# design.net
KiCad netlist of a schematic drawn in Altium Designer
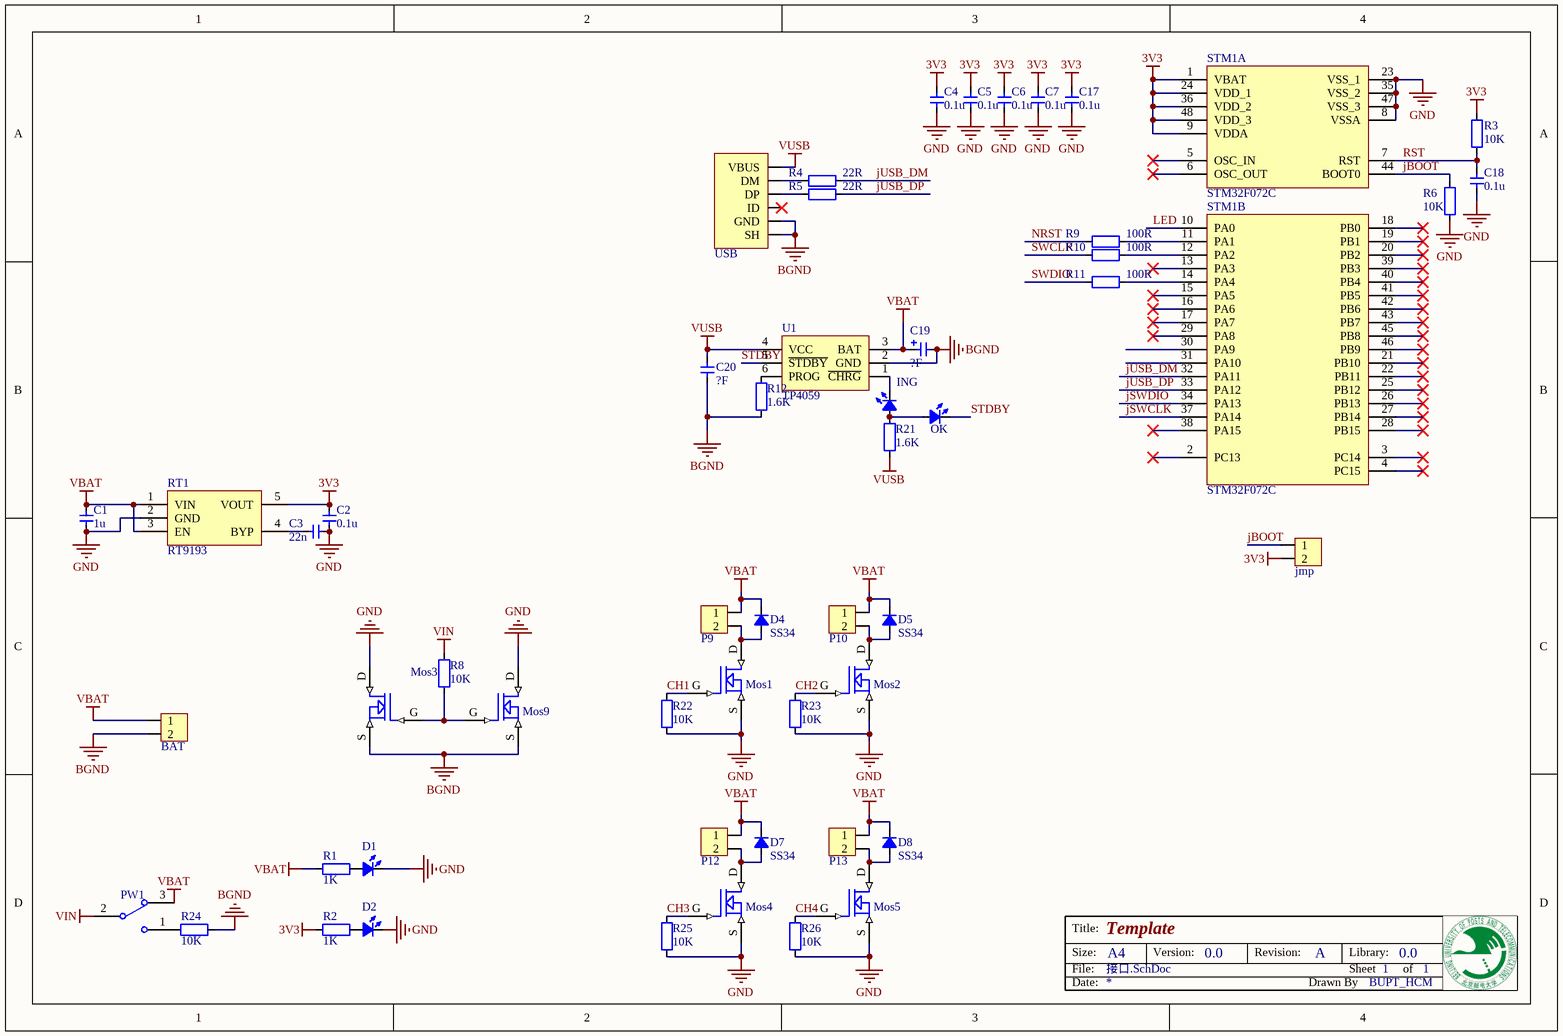
[diagram p0: 接口.SchDoc]

(export (version "E")
  (design (tool "Eeschema 10.0.6"))
  (components
    (comp (ref "BAT")
      (value "HDR1x2_2.54")
      (footprint "PCB_ConnectorHDR:HDR1X2_2.54_90")
      (description "Header")
      (libsource (lib "SCH_ConnectorHDR") (part "HDR1x2_2.54"))
    )
    (comp (ref "C1")
      (value "1u")
      (footprint "PCB_PassiveCap:CAP_0603")
      (description "Capacitor")
      (fields (field (name "Comment") "Cap_0603"))
      (libsource (lib "SCH_Passive") (part "Cap_0603"))
    )
    (comp (ref "C2")
      (value "0.1u")
      (footprint "PCB_PassiveCap:CAP_0603")
      (description "Capacitor")
      (fields (field (name "Comment") "Cap_0603"))
      (libsource (lib "SCH_Passive") (part "Cap_0603"))
    )
    (comp (ref "C3")
      (value "22n")
      (footprint "PCB_PassiveCap:CAP_0603")
      (description "Capacitor")
      (fields (field (name "Comment") "Cap_0603"))
      (libsource (lib "SCH_Passive") (part "Cap_0603"))
    )
    (comp (ref "C4")
      (value "0.1u")
      (footprint "PCB_PassiveCap:CAP_0603")
      (description "Capacitor")
      (fields (field (name "Comment") "Cap_0603"))
      (libsource (lib "SCH_Passive") (part "Cap_0603"))
    )
    (comp (ref "C5")
      (value "0.1u")
      (footprint "PCB_PassiveCap:CAP_0603")
      (description "Capacitor")
      (fields (field (name "Comment") "Cap_0603"))
      (libsource (lib "SCH_Passive") (part "Cap_0603"))
    )
    (comp (ref "C6")
      (value "0.1u")
      (footprint "PCB_PassiveCap:CAP_0603")
      (description "Capacitor")
      (fields (field (name "Comment") "Cap_0603"))
      (libsource (lib "SCH_Passive") (part "Cap_0603"))
    )
    (comp (ref "C7")
      (value "0.1u")
      (footprint "PCB_PassiveCap:CAP_0603")
      (description "Capacitor")
      (fields (field (name "Comment") "Cap_0603"))
      (libsource (lib "SCH_Passive") (part "Cap_0603"))
    )
    (comp (ref "C17")
      (value "0.1u")
      (footprint "PCB_PassiveCap:CAP_0603")
      (description "Capacitor")
      (fields (field (name "Comment") "Cap_0603"))
      (libsource (lib "SCH_Passive") (part "Cap_0603"))
    )
    (comp (ref "C18")
      (value "0.1u")
      (footprint "PCB_PassiveCap:CAP_0603")
      (description "Capacitor")
      (fields (field (name "Comment") "Cap_0603"))
      (libsource (lib "SCH_Passive") (part "Cap_0603"))
    )
    (comp (ref "C19")
      (value "?F")
      (footprint "PCB_PassiveCap:CAP_TAN_D2917")
      (description "Capacitor")
      (fields (field (name "Comment") "Cap_Tan_2917"))
      (libsource (lib "SCH_Passive") (part "Cap_Tan_2917"))
    )
    (comp (ref "C20")
      (value "?F")
      (footprint "PCB_PassiveCap:CAP_0805")
      (description "Capacitor")
      (fields (field (name "Comment") "Cap_0805"))
      (libsource (lib "SCH_Passive") (part "Cap_0805"))
    )
    (comp (ref "D1")
      (value "LED_0805")
      (footprint "PCB_ActiveLED:LED_0805_YELLOW")
      (description "LED")
      (libsource (lib "SCH_Active") (part "LED_0805"))
    )
    (comp (ref "D2")
      (value "LED_0805")
      (footprint "PCB_ActiveLED:LED_0805_YELLOW")
      (description "LED")
      (libsource (lib "SCH_Active") (part "LED_0805"))
    )
    (comp (ref "D4")
      (value "SS34")
      (footprint "PCB_ActiveDIO:DO-214AC")
      (description "Diode")
      (fields (field (name "Comment") "Diode_SMA"))
      (libsource (lib "SCH_Active") (part "Diode_SMA"))
    )
    (comp (ref "D5")
      (value "SS34")
      (footprint "PCB_ActiveDIO:DO-214AC")
      (description "Diode")
      (fields (field (name "Comment") "Diode_SMA"))
      (libsource (lib "SCH_Active") (part "Diode_SMA"))
    )
    (comp (ref "D7")
      (value "SS34")
      (footprint "PCB_ActiveDIO:DO-214AC")
      (description "Diode")
      (fields (field (name "Comment") "Diode_SMA"))
      (libsource (lib "SCH_Active") (part "Diode_SMA"))
    )
    (comp (ref "D8")
      (value "SS34")
      (footprint "PCB_ActiveDIO:DO-214AC")
      (description "Diode")
      (fields (field (name "Comment") "Diode_SMA"))
      (libsource (lib "SCH_Active") (part "Diode_SMA"))
    )
    (comp (ref "ING")
      (value "LED_0805")
      (footprint "PCB_ActiveLED:LED_0805_RED")
      (description "LED")
      (libsource (lib "SCH_Active") (part "LED_0805"))
    )
    (comp (ref "jmp")
      (value "HDR1x2_2.54")
      (footprint "PCB_ConnectorHDR:HDR1X2_2.54_180")
      (description "Header")
      (libsource (lib "SCH_ConnectorHDR") (part "HDR1x2_2.54"))
    )
    (comp (ref "Mos1")
      (value "MOSFET N")
      (footprint "Nmos_SOT23")
      (description "MOS SOT23")
      (libsource (lib "SCH_Active") (part "MOSFET N"))
    )
    (comp (ref "Mos2")
      (value "MOSFET N")
      (footprint "Nmos_SOT23")
      (description "MOS SOT23")
      (libsource (lib "SCH_Active") (part "MOSFET N"))
    )
    (comp (ref "Mos3")
      (value "MOSFET N")
      (footprint "Nmos_SOT23")
      (description "MOS SOT23")
      (libsource (lib "SCH_Active") (part "MOSFET N"))
    )
    (comp (ref "Mos4")
      (value "MOSFET N")
      (footprint "Nmos_SOT23")
      (description "MOS SOT23")
      (libsource (lib "SCH_Active") (part "MOSFET N"))
    )
    (comp (ref "Mos5")
      (value "MOSFET N")
      (footprint "Nmos_SOT23")
      (description "MOS SOT23")
      (libsource (lib "SCH_Active") (part "MOSFET N"))
    )
    (comp (ref "Mos9")
      (value "MOSFET N")
      (footprint "Nmos_SOT23")
      (description "MOS SOT23")
      (libsource (lib "SCH_Active") (part "MOSFET N"))
    )
    (comp (ref "OK")
      (value "LED_0805")
      (footprint "PCB_ActiveLED:LED_0805_GREEN")
      (description "LED")
      (libsource (lib "SCH_Active") (part "LED_0805"))
    )
    (comp (ref "P9")
      (value "HDR1x2_2.54")
      (footprint "PCB_ConnectorHDR:HDR1X2_2.54_180")
      (description "Header")
      (libsource (lib "SCH_ConnectorHDR") (part "HDR1x2_2.54T"))
    )
    (comp (ref "P10")
      (value "HDR1x2_2.54")
      (footprint "PCB_ConnectorHDR:HDR1X2_2.54_180")
      (description "Header")
      (libsource (lib "SCH_ConnectorHDR") (part "HDR1x2_2.54T"))
    )
    (comp (ref "P12")
      (value "HDR1x2_2.54")
      (footprint "PCB_ConnectorHDR:HDR1X2_2.54_180")
      (description "Header")
      (libsource (lib "SCH_ConnectorHDR") (part "HDR1x2_2.54T"))
    )
    (comp (ref "P13")
      (value "HDR1x2_2.54")
      (footprint "PCB_ConnectorHDR:HDR1X2_2.54_180")
      (description "Header")
      (libsource (lib "SCH_ConnectorHDR") (part "HDR1x2_2.54T"))
    )
    (comp (ref "PW1")
      (value "SwitchSPDT_2.8x6.6_90")
      (footprint "PCB_Switch:SwitchSPDT_2.8X6.6_90")
      (description "Switch")
      (libsource (lib "SCH_Switch") (part "SwitchSPDT_2.8x6.6_90"))
    )
    (comp (ref "R1")
      (value "1K")
      (footprint "PCB_PassiveRes:RES_0603")
      (description "Resistor")
      (fields (field (name "Comment") "Res_0603"))
      (libsource (lib "SCH_Passive") (part "Res_0603"))
    )
    (comp (ref "R2")
      (value "1K")
      (footprint "PCB_PassiveRes:RES_0603")
      (description "Resistor")
      (fields (field (name "Comment") "Res_0603"))
      (libsource (lib "SCH_Passive") (part "Res_0603"))
    )
    (comp (ref "R3")
      (value "10K")
      (footprint "PCB_PassiveRes:RES_0603")
      (description "Resistor")
      (fields (field (name "Comment") "Res_0603"))
      (libsource (lib "") (part "Res_0603_1"))
    )
    (comp (ref "R4")
      (value "22R")
      (footprint "PCB_PassiveRes:RES_0603")
      (description "Resistor")
      (fields (field (name "Comment") "Res_0603"))
      (libsource (lib "SCH_Passive") (part "Res_0603"))
    )
    (comp (ref "R5")
      (value "22R")
      (footprint "PCB_PassiveRes:RES_0603")
      (description "Resistor")
      (fields (field (name "Comment") "Res_0603"))
      (libsource (lib "SCH_Passive") (part "Res_0603"))
    )
    (comp (ref "R6")
      (value "10K")
      (footprint "PCB_PassiveRes:RES_0603")
      (description "Resistor")
      (fields (field (name "Comment") "Res_0603"))
      (libsource (lib "") (part "Res_0603_1"))
    )
    (comp (ref "R8")
      (value "10K")
      (footprint "PCB_PassiveRes:RES_0603")
      (description "Resistor")
      (fields (field (name "Comment") "Res_0603"))
      (libsource (lib "") (part "Res_0603_1"))
    )
    (comp (ref "R9")
      (value "100R")
      (footprint "PCB_PassiveRes:RES_0603")
      (description "Resistor")
      (fields (field (name "Comment") "Res_0603"))
      (libsource (lib "SCH_Passive") (part "Res_0603"))
    )
    (comp (ref "R10")
      (value "100R")
      (footprint "PCB_PassiveRes:RES_0603")
      (description "Resistor")
      (fields (field (name "Comment") "Res_0603"))
      (libsource (lib "SCH_Passive") (part "Res_0603"))
    )
    (comp (ref "R11")
      (value "100R")
      (footprint "PCB_PassiveRes:RES_0603")
      (description "Resistor")
      (fields (field (name "Comment") "Res_0603"))
      (libsource (lib "SCH_Passive") (part "Res_0603"))
    )
    (comp (ref "R12")
      (value "1.6K")
      (footprint "PCB_PassiveRes:RES_0603")
      (description "Resistor")
      (fields (field (name "Comment") "Res_0603"))
      (libsource (lib "") (part "Res_0603_2"))
    )
    (comp (ref "R21")
      (value "1.6K")
      (footprint "PCB_PassiveRes:RES_0603")
      (description "Resistor")
      (fields (field (name "Comment") "Res_0603"))
      (libsource (lib "") (part "Res_0603_2"))
    )
    (comp (ref "R22")
      (value "10K")
      (footprint "PCB_PassiveRes:RES_0603")
      (description "Resistor")
      (fields (field (name "Comment") "Res_0603"))
      (libsource (lib "") (part "Res_0603_1"))
    )
    (comp (ref "R23")
      (value "10K")
      (footprint "PCB_PassiveRes:RES_0603")
      (description "Resistor")
      (fields (field (name "Comment") "Res_0603"))
      (libsource (lib "") (part "Res_0603_1"))
    )
    (comp (ref "R24")
      (value "10K")
      (footprint "PCB_PassiveRes:RES_0603")
      (description "Resistor")
      (fields (field (name "Comment") "Res_0603"))
      (libsource (lib "SCH_Passive") (part "Res_0603"))
    )
    (comp (ref "R25")
      (value "10K")
      (footprint "PCB_PassiveRes:RES_0603")
      (description "Resistor")
      (fields (field (name "Comment") "Res_0603"))
      (libsource (lib "") (part "Res_0603_1"))
    )
    (comp (ref "R26")
      (value "10K")
      (footprint "PCB_PassiveRes:RES_0603")
      (description "Resistor")
      (fields (field (name "Comment") "Res_0603"))
      (libsource (lib "") (part "Res_0603_1"))
    )
    (comp (ref "RT1")
      (value "RT9193")
      (footprint "PCB_IntegratedCircuit:SOT23-5")
      (description "Power")
      (libsource (lib "SCH_IntegratedCircuit") (part "RT9193"))
    )
    (comp (ref "STM1")
      (value "STM32F072C")
      (footprint "PCB_IntegratedCircuit:LQFP_P0.5_48")
      (description "MCU")
      (libsource (lib "SCH_IntegratedCircuit") (part "STM32F103C"))
    )
    (comp (ref "U1")
      (value "TP4059")
      (footprint "SOT23-6")
      (libsource (lib "SCH_IntegratedCircuit") (part "TP4059"))
    )
    (comp (ref "USB")
      (value "USB_Micro")
      (footprint "PCB_USB:USB_Micro-AB")
      (description "USB")
      (libsource (lib "SCH_USB") (part "USB_Micro"))
    )
  )
  (nets
    (net (code "1") (name "/CH1") (class "Default")
      (node (ref "Mos1") (pin "G") (pinfunction "G_G") (pintype "input"))
      (node (ref "R22") (pin "2") (pinfunction "2_2") (pintype "passive"))
    )
    (net (code "2") (name "/CH2") (class "Default")
      (node (ref "Mos2") (pin "G") (pinfunction "G_G") (pintype "input"))
      (node (ref "R23") (pin "2") (pinfunction "2_2") (pintype "passive"))
    )
    (net (code "3") (name "/CH3") (class "Default")
      (node (ref "Mos4") (pin "G") (pinfunction "G_G") (pintype "input"))
      (node (ref "R25") (pin "2") (pinfunction "2_2") (pintype "passive"))
    )
    (net (code "4") (name "/CH4") (class "Default")
      (node (ref "Mos5") (pin "G") (pinfunction "G_G") (pintype "input"))
      (node (ref "R26") (pin "2") (pinfunction "2_2") (pintype "passive"))
    )
    (net (code "5") (name "/LED") (class "Default")
      (node (ref "STM1") (pin "10") (pinfunction "PA0_10") (pintype "passive"))
    )
    (net (code "6") (name "/NRST") (class "Default")
      (node (ref "R9") (pin "1") (pinfunction "1_1") (pintype "passive"))
    )
    (net (code "7") (name "/RST") (class "Default")
      (node (ref "C18") (pin "2") (pinfunction "2_2") (pintype "passive"))
      (node (ref "R3") (pin "1") (pinfunction "1_1") (pintype "passive"))
      (node (ref "STM1") (pin "7") (pinfunction "RST_7") (pintype "passive"))
    )
    (net (code "8") (name "/STDBY") (class "Default")
      (node (ref "OK") (pin "2") (pinfunction "K_2") (pintype "passive"))
      (node (ref "U1") (pin "5") (pinfunction "~{STDBY}_5") (pintype "passive"))
    )
    (net (code "9") (name "/SWCLK") (class "Default")
      (node (ref "R10") (pin "1") (pinfunction "1_1") (pintype "passive"))
    )
    (net (code "10") (name "/SWDIO") (class "Default")
      (node (ref "R11") (pin "1") (pinfunction "1_1") (pintype "passive"))
    )
    (net (code "11") (name "/jBOOT") (class "Default")
      (node (ref "R6") (pin "2") (pinfunction "2_2") (pintype "passive"))
      (node (ref "STM1") (pin "44") (pinfunction "BOOT0_44") (pintype "passive"))
      (node (ref "jmp") (pin "1") (pinfunction "1_1") (pintype "passive"))
    )
    (net (code "12") (name "/jSWCLK") (class "Default")
      (node (ref "STM1") (pin "37") (pinfunction "PA14_37") (pintype "passive"))
    )
    (net (code "13") (name "/jSWDIO") (class "Default")
      (node (ref "STM1") (pin "34") (pinfunction "PA13_34") (pintype "passive"))
    )
    (net (code "14") (name "/jUSB_DM") (class "Default")
      (node (ref "R4") (pin "2") (pinfunction "2_2") (pintype "passive"))
      (node (ref "STM1") (pin "32") (pinfunction "PA11_32") (pintype "passive"))
    )
    (net (code "15") (name "/jUSB_DP") (class "Default")
      (node (ref "R5") (pin "2") (pinfunction "2_2") (pintype "passive"))
      (node (ref "STM1") (pin "33") (pinfunction "PA12_33") (pintype "passive"))
    )
    (net (code "16") (name "3V3") (class "Default")
      (node (ref "C17") (pin "2") (pinfunction "2_2") (pintype "passive"))
      (node (ref "C2") (pin "2") (pinfunction "2_2") (pintype "passive"))
      (node (ref "C4") (pin "1") (pinfunction "1_1") (pintype "passive"))
      (node (ref "C5") (pin "1") (pinfunction "1_1") (pintype "passive"))
      (node (ref "C6") (pin "1") (pinfunction "1_1") (pintype "passive"))
      (node (ref "C7") (pin "1") (pinfunction "1_1") (pintype "passive"))
      (node (ref "R2") (pin "1") (pinfunction "1_1") (pintype "passive"))
      (node (ref "R3") (pin "2") (pinfunction "2_2") (pintype "passive"))
      (node (ref "RT1") (pin "5") (pinfunction "VOUT_5") (pintype "passive"))
      (node (ref "STM1") (pin "1") (pinfunction "VBAT_1") (pintype "passive"))
      (node (ref "STM1") (pin "24") (pinfunction "VDD_1_24") (pintype "passive"))
      (node (ref "STM1") (pin "36") (pinfunction "VDD_2_36") (pintype "passive"))
      (node (ref "STM1") (pin "48") (pinfunction "VDD_3_48") (pintype "passive"))
      (node (ref "STM1") (pin "9") (pinfunction "VDDA_9") (pintype "passive"))
      (node (ref "jmp") (pin "2") (pinfunction "2_2") (pintype "passive"))
    )
    (net (code "17") (name "BGND") (class "Default")
      (node (ref "BAT") (pin "2") (pinfunction "2_2") (pintype "passive"))
      (node (ref "C19") (pin "2") (pinfunction "2_2") (pintype "passive"))
      (node (ref "C20") (pin "1") (pinfunction "1_1") (pintype "passive"))
      (node (ref "Mos3") (pin "S") (pinfunction "S_S") (pintype "input"))
      (node (ref "Mos9") (pin "S") (pinfunction "S_S") (pintype "input"))
      (node (ref "R12") (pin "2") (pinfunction "2_2") (pintype "passive"))
      (node (ref "R24") (pin "2") (pinfunction "2_2") (pintype "passive"))
      (node (ref "U1") (pin "2") (pinfunction "GND_2") (pintype "passive"))
      (node (ref "USB") (pin "0") (pinfunction "SH_0") (pintype "passive"))
      (node (ref "USB") (pin "5") (pinfunction "GND_5") (pintype "passive"))
    )
    (net (code "18") (name "GND") (class "Default")
      (node (ref "C1") (pin "1") (pinfunction "1_1") (pintype "passive"))
      (node (ref "C17") (pin "1") (pinfunction "1_1") (pintype "passive"))
      (node (ref "C18") (pin "1") (pinfunction "1_1") (pintype "passive"))
      (node (ref "C2") (pin "1") (pinfunction "1_1") (pintype "passive"))
      (node (ref "C3") (pin "1") (pinfunction "1_1") (pintype "passive"))
      (node (ref "C4") (pin "2") (pinfunction "2_2") (pintype "passive"))
      (node (ref "C5") (pin "2") (pinfunction "2_2") (pintype "passive"))
      (node (ref "C6") (pin "2") (pinfunction "2_2") (pintype "passive"))
      (node (ref "C7") (pin "2") (pinfunction "2_2") (pintype "passive"))
      (node (ref "D1") (pin "2") (pinfunction "K_2") (pintype "passive"))
      (node (ref "D2") (pin "2") (pinfunction "K_2") (pintype "passive"))
      (node (ref "Mos1") (pin "S") (pinfunction "S_S") (pintype "input"))
      (node (ref "Mos2") (pin "S") (pinfunction "S_S") (pintype "input"))
      (node (ref "Mos3") (pin "D") (pinfunction "D_D") (pintype "input"))
      (node (ref "Mos4") (pin "S") (pinfunction "S_S") (pintype "input"))
      (node (ref "Mos5") (pin "S") (pinfunction "S_S") (pintype "input"))
      (node (ref "Mos9") (pin "D") (pinfunction "D_D") (pintype "input"))
      (node (ref "R22") (pin "1") (pinfunction "1_1") (pintype "passive"))
      (node (ref "R23") (pin "1") (pinfunction "1_1") (pintype "passive"))
      (node (ref "R25") (pin "1") (pinfunction "1_1") (pintype "passive"))
      (node (ref "R26") (pin "1") (pinfunction "1_1") (pintype "passive"))
      (node (ref "R6") (pin "1") (pinfunction "1_1") (pintype "passive"))
      (node (ref "RT1") (pin "2") (pinfunction "GND_2") (pintype "passive"))
      (node (ref "STM1") (pin "23") (pinfunction "VSS_1_23") (pintype "passive"))
      (node (ref "STM1") (pin "35") (pinfunction "VSS_2_35") (pintype "passive"))
      (node (ref "STM1") (pin "47") (pinfunction "VSS_3_47") (pintype "passive"))
      (node (ref "STM1") (pin "8") (pinfunction "VSSA_8") (pintype "passive"))
    )
    (net (code "19") (name "Net-(D1-A)") (class "Default")
      (node (ref "D1") (pin "1") (pinfunction "A_1") (pintype "passive"))
      (node (ref "R1") (pin "2") (pinfunction "2_2") (pintype "passive"))
    )
    (net (code "20") (name "Net-(D2-A)") (class "Default")
      (node (ref "D2") (pin "1") (pinfunction "A_1") (pintype "passive"))
      (node (ref "R2") (pin "2") (pinfunction "2_2") (pintype "passive"))
    )
    (net (code "21") (name "Net-(D4-A)") (class "Default")
      (node (ref "D4") (pin "1") (pinfunction "A_1") (pintype "passive"))
      (node (ref "Mos1") (pin "D") (pinfunction "D_D") (pintype "input"))
      (node (ref "P9") (pin "2") (pinfunction "2_2") (pintype "passive"))
    )
    (net (code "22") (name "Net-(D5-A)") (class "Default")
      (node (ref "D5") (pin "1") (pinfunction "A_1") (pintype "passive"))
      (node (ref "Mos2") (pin "D") (pinfunction "D_D") (pintype "input"))
      (node (ref "P10") (pin "2") (pinfunction "2_2") (pintype "passive"))
    )
    (net (code "23") (name "Net-(D7-A)") (class "Default")
      (node (ref "D7") (pin "1") (pinfunction "A_1") (pintype "passive"))
      (node (ref "Mos4") (pin "D") (pinfunction "D_D") (pintype "input"))
      (node (ref "P12") (pin "2") (pinfunction "2_2") (pintype "passive"))
    )
    (net (code "24") (name "Net-(D8-A)") (class "Default")
      (node (ref "D8") (pin "1") (pinfunction "A_1") (pintype "passive"))
      (node (ref "Mos5") (pin "D") (pinfunction "D_D") (pintype "input"))
      (node (ref "P13") (pin "2") (pinfunction "2_2") (pintype "passive"))
    )
    (net (code "25") (name "Net-(ING-A)") (class "Default")
      (node (ref "ING") (pin "1") (pinfunction "A_1") (pintype "passive"))
      (node (ref "OK") (pin "1") (pinfunction "A_1") (pintype "passive"))
      (node (ref "R21") (pin "1") (pinfunction "1_1") (pintype "passive"))
    )
    (net (code "26") (name "Net-(ING-K)") (class "Default")
      (node (ref "ING") (pin "2") (pinfunction "K_2") (pintype "passive"))
      (node (ref "U1") (pin "1") (pinfunction "~{CHRG}_1") (pintype "passive"))
    )
    (net (code "27") (name "Net-(Mos3-PadG)") (class "Default")
      (node (ref "Mos3") (pin "G") (pinfunction "G_G") (pintype "input"))
      (node (ref "Mos9") (pin "G") (pinfunction "G_G") (pintype "input"))
      (node (ref "R8") (pin "1") (pinfunction "1_1") (pintype "passive"))
    )
    (net (code "28") (name "Net-(PW1-Pad1)") (class "Default")
      (node (ref "PW1") (pin "1") (pinfunction "1_1") (pintype "passive"))
      (node (ref "R24") (pin "1") (pinfunction "1_1") (pintype "passive"))
    )
    (net (code "29") (name "Net-(RT1-BYP)") (class "Default")
      (node (ref "C3") (pin "2") (pinfunction "2_2") (pintype "passive"))
      (node (ref "RT1") (pin "4") (pinfunction "BYP_4") (pintype "passive"))
    )
    (net (code "30") (name "Net-(STM1B-PA1)") (class "Default")
      (node (ref "R9") (pin "2") (pinfunction "2_2") (pintype "passive"))
      (node (ref "STM1") (pin "11") (pinfunction "PA1_11") (pintype "passive"))
    )
    (net (code "31") (name "Net-(STM1B-PA2)") (class "Default")
      (node (ref "R10") (pin "2") (pinfunction "2_2") (pintype "passive"))
      (node (ref "STM1") (pin "12") (pinfunction "PA2_12") (pintype "passive"))
    )
    (net (code "32") (name "Net-(STM1B-PA4)") (class "Default")
      (node (ref "R11") (pin "2") (pinfunction "2_2") (pintype "passive"))
      (node (ref "STM1") (pin "14") (pinfunction "PA4_14") (pintype "passive"))
    )
    (net (code "33") (name "Net-(U1-PROG)") (class "Default")
      (node (ref "R12") (pin "1") (pinfunction "1_1") (pintype "passive"))
      (node (ref "U1") (pin "6") (pinfunction "PROG_6") (pintype "passive"))
    )
    (net (code "34") (name "Net-(USB-DM)") (class "Default")
      (node (ref "R4") (pin "1") (pinfunction "1_1") (pintype "passive"))
      (node (ref "USB") (pin "2") (pinfunction "DM_2") (pintype "passive"))
    )
    (net (code "35") (name "Net-(USB-DP)") (class "Default")
      (node (ref "R5") (pin "1") (pinfunction "1_1") (pintype "passive"))
      (node (ref "USB") (pin "3") (pinfunction "DP_3") (pintype "passive"))
    )
    (net (code "36") (name "VBAT") (class "Default")
      (node (ref "BAT") (pin "1") (pinfunction "1_1") (pintype "passive"))
      (node (ref "C1") (pin "2") (pinfunction "2_2") (pintype "passive"))
      (node (ref "C19") (pin "1") (pinfunction "1_1") (pintype "passive"))
      (node (ref "D4") (pin "2") (pinfunction "K_2") (pintype "passive"))
      (node (ref "D5") (pin "2") (pinfunction "K_2") (pintype "passive"))
      (node (ref "D7") (pin "2") (pinfunction "K_2") (pintype "passive"))
      (node (ref "D8") (pin "2") (pinfunction "K_2") (pintype "passive"))
      (node (ref "P10") (pin "1") (pinfunction "1_1") (pintype "passive"))
      (node (ref "P12") (pin "1") (pinfunction "1_1") (pintype "passive"))
      (node (ref "P13") (pin "1") (pinfunction "1_1") (pintype "passive"))
      (node (ref "P9") (pin "1") (pinfunction "1_1") (pintype "passive"))
      (node (ref "PW1") (pin "3") (pinfunction "3_3") (pintype "passive"))
      (node (ref "R1") (pin "1") (pinfunction "1_1") (pintype "passive"))
      (node (ref "RT1") (pin "1") (pinfunction "VIN_1") (pintype "passive"))
      (node (ref "RT1") (pin "3") (pinfunction "EN_3") (pintype "power_in"))
      (node (ref "U1") (pin "3") (pinfunction "BAT_3") (pintype "passive"))
    )
    (net (code "37") (name "VIN") (class "Default")
      (node (ref "PW1") (pin "2") (pinfunction "2_2") (pintype "passive"))
      (node (ref "R8") (pin "2") (pinfunction "2_2") (pintype "passive"))
    )
    (net (code "38") (name "VUSB") (class "Default")
      (node (ref "C20") (pin "2") (pinfunction "2_2") (pintype "passive"))
      (node (ref "R21") (pin "2") (pinfunction "2_2") (pintype "passive"))
      (node (ref "U1") (pin "4") (pinfunction "VCC_4") (pintype "passive"))
      (node (ref "USB") (pin "1") (pinfunction "VBUS_1") (pintype "passive"))
    )
    (net (code "39") (name "unconnected-(STM1A-OSC_IN-Pad5)") (class "Default")
      (node (ref "STM1") (pin "5") (pinfunction "OSC_IN_5") (pintype "passive+no_connect"))
    )
    (net (code "40") (name "unconnected-(STM1A-OSC_OUT-Pad6)") (class "Default")
      (node (ref "STM1") (pin "6") (pinfunction "OSC_OUT_6") (pintype "passive+no_connect"))
    )
    (net (code "41") (name "unconnected-(STM1B-PA3-Pad13)") (class "Default")
      (node (ref "STM1") (pin "13") (pinfunction "PA3_13") (pintype "passive+no_connect"))
    )
    (net (code "42") (name "unconnected-(STM1B-PA5-Pad15)") (class "Default")
      (node (ref "STM1") (pin "15") (pinfunction "PA5_15") (pintype "passive+no_connect"))
    )
    (net (code "43") (name "unconnected-(STM1B-PA6-Pad16)") (class "Default")
      (node (ref "STM1") (pin "16") (pinfunction "PA6_16") (pintype "passive+no_connect"))
    )
    (net (code "44") (name "unconnected-(STM1B-PA7-Pad17)") (class "Default")
      (node (ref "STM1") (pin "17") (pinfunction "PA7_17") (pintype "passive+no_connect"))
    )
    (net (code "45") (name "unconnected-(STM1B-PA8-Pad29)") (class "Default")
      (node (ref "STM1") (pin "29") (pinfunction "PA8_29") (pintype "passive+no_connect"))
    )
    (net (code "46") (name "unconnected-(STM1B-PA9-Pad30)") (class "Default")
      (node (ref "STM1") (pin "30") (pinfunction "PA9_30") (pintype "passive"))
    )
    (net (code "47") (name "unconnected-(STM1B-PA10-Pad31)") (class "Default")
      (node (ref "STM1") (pin "31") (pinfunction "PA10_31") (pintype "passive"))
    )
    (net (code "48") (name "unconnected-(STM1B-PA15-Pad38)") (class "Default")
      (node (ref "STM1") (pin "38") (pinfunction "PA15_38") (pintype "passive+no_connect"))
    )
    (net (code "49") (name "unconnected-(STM1B-PB0-Pad18)") (class "Default")
      (node (ref "STM1") (pin "18") (pinfunction "PB0_18") (pintype "passive+no_connect"))
    )
    (net (code "50") (name "unconnected-(STM1B-PB1-Pad19)") (class "Default")
      (node (ref "STM1") (pin "19") (pinfunction "PB1_19") (pintype "passive+no_connect"))
    )
    (net (code "51") (name "unconnected-(STM1B-PB2-Pad20)") (class "Default")
      (node (ref "STM1") (pin "20") (pinfunction "PB2_20") (pintype "passive+no_connect"))
    )
    (net (code "52") (name "unconnected-(STM1B-PB3-Pad39)") (class "Default")
      (node (ref "STM1") (pin "39") (pinfunction "PB3_39") (pintype "passive+no_connect"))
    )
    (net (code "53") (name "unconnected-(STM1B-PB4-Pad40)") (class "Default")
      (node (ref "STM1") (pin "40") (pinfunction "PB4_40") (pintype "passive+no_connect"))
    )
    (net (code "54") (name "unconnected-(STM1B-PB5-Pad41)") (class "Default")
      (node (ref "STM1") (pin "41") (pinfunction "PB5_41") (pintype "passive+no_connect"))
    )
    (net (code "55") (name "unconnected-(STM1B-PB6-Pad42)") (class "Default")
      (node (ref "STM1") (pin "42") (pinfunction "PB6_42") (pintype "passive+no_connect"))
    )
    (net (code "56") (name "unconnected-(STM1B-PB7-Pad43)") (class "Default")
      (node (ref "STM1") (pin "43") (pinfunction "PB7_43") (pintype "passive+no_connect"))
    )
    (net (code "57") (name "unconnected-(STM1B-PB8-Pad45)") (class "Default")
      (node (ref "STM1") (pin "45") (pinfunction "PB8_45") (pintype "passive+no_connect"))
    )
    (net (code "58") (name "unconnected-(STM1B-PB9-Pad46)") (class "Default")
      (node (ref "STM1") (pin "46") (pinfunction "PB9_46") (pintype "passive+no_connect"))
    )
    (net (code "59") (name "unconnected-(STM1B-PB10-Pad21)") (class "Default")
      (node (ref "STM1") (pin "21") (pinfunction "PB10_21") (pintype "passive+no_connect"))
    )
    (net (code "60") (name "unconnected-(STM1B-PB11-Pad22)") (class "Default")
      (node (ref "STM1") (pin "22") (pinfunction "PB11_22") (pintype "passive+no_connect"))
    )
    (net (code "61") (name "unconnected-(STM1B-PB12-Pad25)") (class "Default")
      (node (ref "STM1") (pin "25") (pinfunction "PB12_25") (pintype "passive+no_connect"))
    )
    (net (code "62") (name "unconnected-(STM1B-PB13-Pad26)") (class "Default")
      (node (ref "STM1") (pin "26") (pinfunction "PB13_26") (pintype "passive+no_connect"))
    )
    (net (code "63") (name "unconnected-(STM1B-PB14-Pad27)") (class "Default")
      (node (ref "STM1") (pin "27") (pinfunction "PB14_27") (pintype "passive+no_connect"))
    )
    (net (code "64") (name "unconnected-(STM1B-PB15-Pad28)") (class "Default")
      (node (ref "STM1") (pin "28") (pinfunction "PB15_28") (pintype "passive+no_connect"))
    )
    (net (code "65") (name "unconnected-(STM1B-PC13-Pad2)") (class "Default")
      (node (ref "STM1") (pin "2") (pinfunction "PC13_2") (pintype "passive+no_connect"))
    )
    (net (code "66") (name "unconnected-(STM1B-PC14-Pad3)") (class "Default")
      (node (ref "STM1") (pin "3") (pinfunction "PC14_3") (pintype "passive+no_connect"))
    )
    (net (code "67") (name "unconnected-(STM1B-PC15-Pad4)") (class "Default")
      (node (ref "STM1") (pin "4") (pinfunction "PC15_4") (pintype "passive+no_connect"))
    )
    (net (code "68") (name "unconnected-(USB-ID-Pad4)") (class "Default")
      (node (ref "USB") (pin "4") (pinfunction "ID_4") (pintype "passive+no_connect"))
    )
  )
)
